# evlogger_current.net
KiCad netlist of a schematic drawn in EAGLE
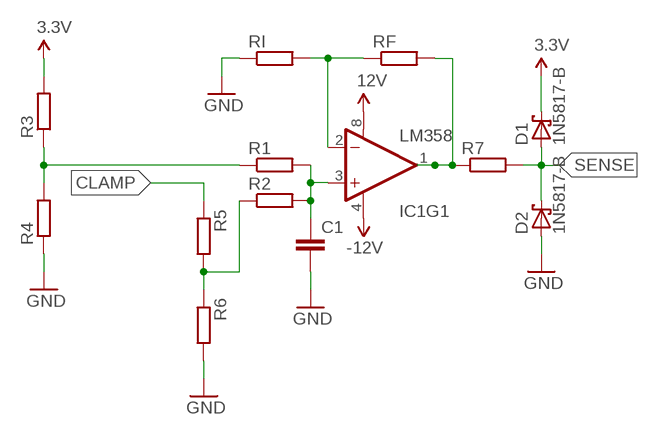
[diagram p0: schematic, sheet 1]

(export (version "E")
  (design (tool "Eeschema 10.0.6"))
  (components
    (comp (ref "C1")
      (value "C-EU025-024X044")
      (footprint "eagle-import:C025-024X044")
      (libsource (lib "eagle-import") (part "C-EU025-024X044"))
    )
    (comp (ref "D1")
      (value "1N5817-B")
      (footprint "eagle-import:DO41-7.6")
      (libsource (lib "eagle-import") (part "1N5817-B"))
    )
    (comp (ref "D2")
      (value "1N5817-B")
      (footprint "eagle-import:DO41-7.6")
      (libsource (lib "eagle-import") (part "1N5817-B"))
    )
    (comp (ref "IC1")
      (value "LM358")
      (footprint "eagle-import:DIP08")
      (libsource (lib "eagle-import") (part "LM358"))
    )
    (comp (ref "R1")
      (value "R-EU_0207/10")
      (footprint "eagle-import:0207_10")
      (libsource (lib "eagle-import") (part "R-EU_0207/10"))
    )
    (comp (ref "R2")
      (value "R-EU_0207/10")
      (footprint "eagle-import:0207_10")
      (libsource (lib "eagle-import") (part "R-EU_0207/10"))
    )
    (comp (ref "R3")
      (value "R-EU_0207/10")
      (footprint "eagle-import:0207_10")
      (libsource (lib "eagle-import") (part "R-EU_0207/10"))
    )
    (comp (ref "R4")
      (value "R-EU_0207/10")
      (footprint "eagle-import:0207_10")
      (libsource (lib "eagle-import") (part "R-EU_0207/10"))
    )
    (comp (ref "R5")
      (value "R-EU_0207/10")
      (footprint "eagle-import:0207_10")
      (libsource (lib "eagle-import") (part "R-EU_0207/10"))
    )
    (comp (ref "R6")
      (value "R-EU_0207/10")
      (footprint "eagle-import:0207_10")
      (libsource (lib "eagle-import") (part "R-EU_0207/10"))
    )
    (comp (ref "R7")
      (value "R-EU_0207/10")
      (footprint "eagle-import:0207_10")
      (libsource (lib "eagle-import") (part "R-EU_0207/10"))
    )
    (comp (ref "RF")
      (value "R-EU_0207/10")
      (footprint "eagle-import:0207_10")
      (libsource (lib "eagle-import") (part "R-EU_0207/10"))
    )
    (comp (ref "RI")
      (value "R-EU_0207/10")
      (footprint "eagle-import:0207_10")
      (libsource (lib "eagle-import") (part "R-EU_0207/10"))
    )
  )
  (nets
    (net (code "1") (name "-12V") (class "Default")
      (node (ref "IC1") (pin "4") (pinfunction "V-_4") (pintype "power_in"))
    )
    (net (code "2") (name "3.3V") (class "Default")
      (node (ref "D1") (pin "C") (pinfunction "C_C") (pintype "passive"))
      (node (ref "R3") (pin "2") (pinfunction "2_2") (pintype "passive"))
    )
    (net (code "3") (name "12V") (class "Default")
      (node (ref "IC1") (pin "8") (pinfunction "V+_8") (pintype "power_in"))
    )
    (net (code "4") (name "CLAMP") (class "Default")
      (node (ref "R5") (pin "1") (pinfunction "1_1") (pintype "passive"))
    )
    (net (code "5") (name "GND") (class "Default")
      (node (ref "C1") (pin "2") (pinfunction "2_2") (pintype "passive"))
      (node (ref "D2") (pin "A") (pinfunction "A_A") (pintype "passive"))
      (node (ref "R4") (pin "1") (pinfunction "1_1") (pintype "passive"))
      (node (ref "R6") (pin "2") (pinfunction "2_2") (pintype "passive"))
      (node (ref "RI") (pin "1") (pinfunction "1_1") (pintype "passive"))
    )
    (net (code "6") (name "Net-(IC1A-+IN)") (class "Default")
      (node (ref "C1") (pin "1") (pinfunction "1_1") (pintype "passive"))
      (node (ref "IC1") (pin "3") (pinfunction "+IN_3") (pintype "input"))
      (node (ref "R1") (pin "2") (pinfunction "2_2") (pintype "passive"))
      (node (ref "R2") (pin "2") (pinfunction "2_2") (pintype "passive"))
    )
    (net (code "7") (name "Net-(IC1A--IN)") (class "Default")
      (node (ref "IC1") (pin "2") (pinfunction "-IN_2") (pintype "input"))
      (node (ref "RF") (pin "1") (pinfunction "1_1") (pintype "passive"))
      (node (ref "RI") (pin "2") (pinfunction "2_2") (pintype "passive"))
    )
    (net (code "8") (name "Net-(IC1A-OUT)") (class "Default")
      (node (ref "IC1") (pin "1") (pinfunction "OUT_1") (pintype "output"))
      (node (ref "R7") (pin "1") (pinfunction "1_1") (pintype "passive"))
      (node (ref "RF") (pin "2") (pinfunction "2_2") (pintype "passive"))
    )
    (net (code "9") (name "Net-(R1-Pad1)") (class "Default")
      (node (ref "R1") (pin "1") (pinfunction "1_1") (pintype "passive"))
      (node (ref "R3") (pin "1") (pinfunction "1_1") (pintype "passive"))
      (node (ref "R4") (pin "2") (pinfunction "2_2") (pintype "passive"))
    )
    (net (code "10") (name "Net-(R2-Pad1)") (class "Default")
      (node (ref "R2") (pin "1") (pinfunction "1_1") (pintype "passive"))
      (node (ref "R5") (pin "2") (pinfunction "2_2") (pintype "passive"))
      (node (ref "R6") (pin "1") (pinfunction "1_1") (pintype "passive"))
    )
    (net (code "11") (name "SENSE") (class "Default")
      (node (ref "D1") (pin "A") (pinfunction "A_A") (pintype "passive"))
      (node (ref "D2") (pin "C") (pinfunction "C_C") (pintype "passive"))
      (node (ref "R7") (pin "2") (pinfunction "2_2") (pintype "passive"))
    )
  )
)
